# scan.net
KiCad netlist of a schematic drawn in EAGLE
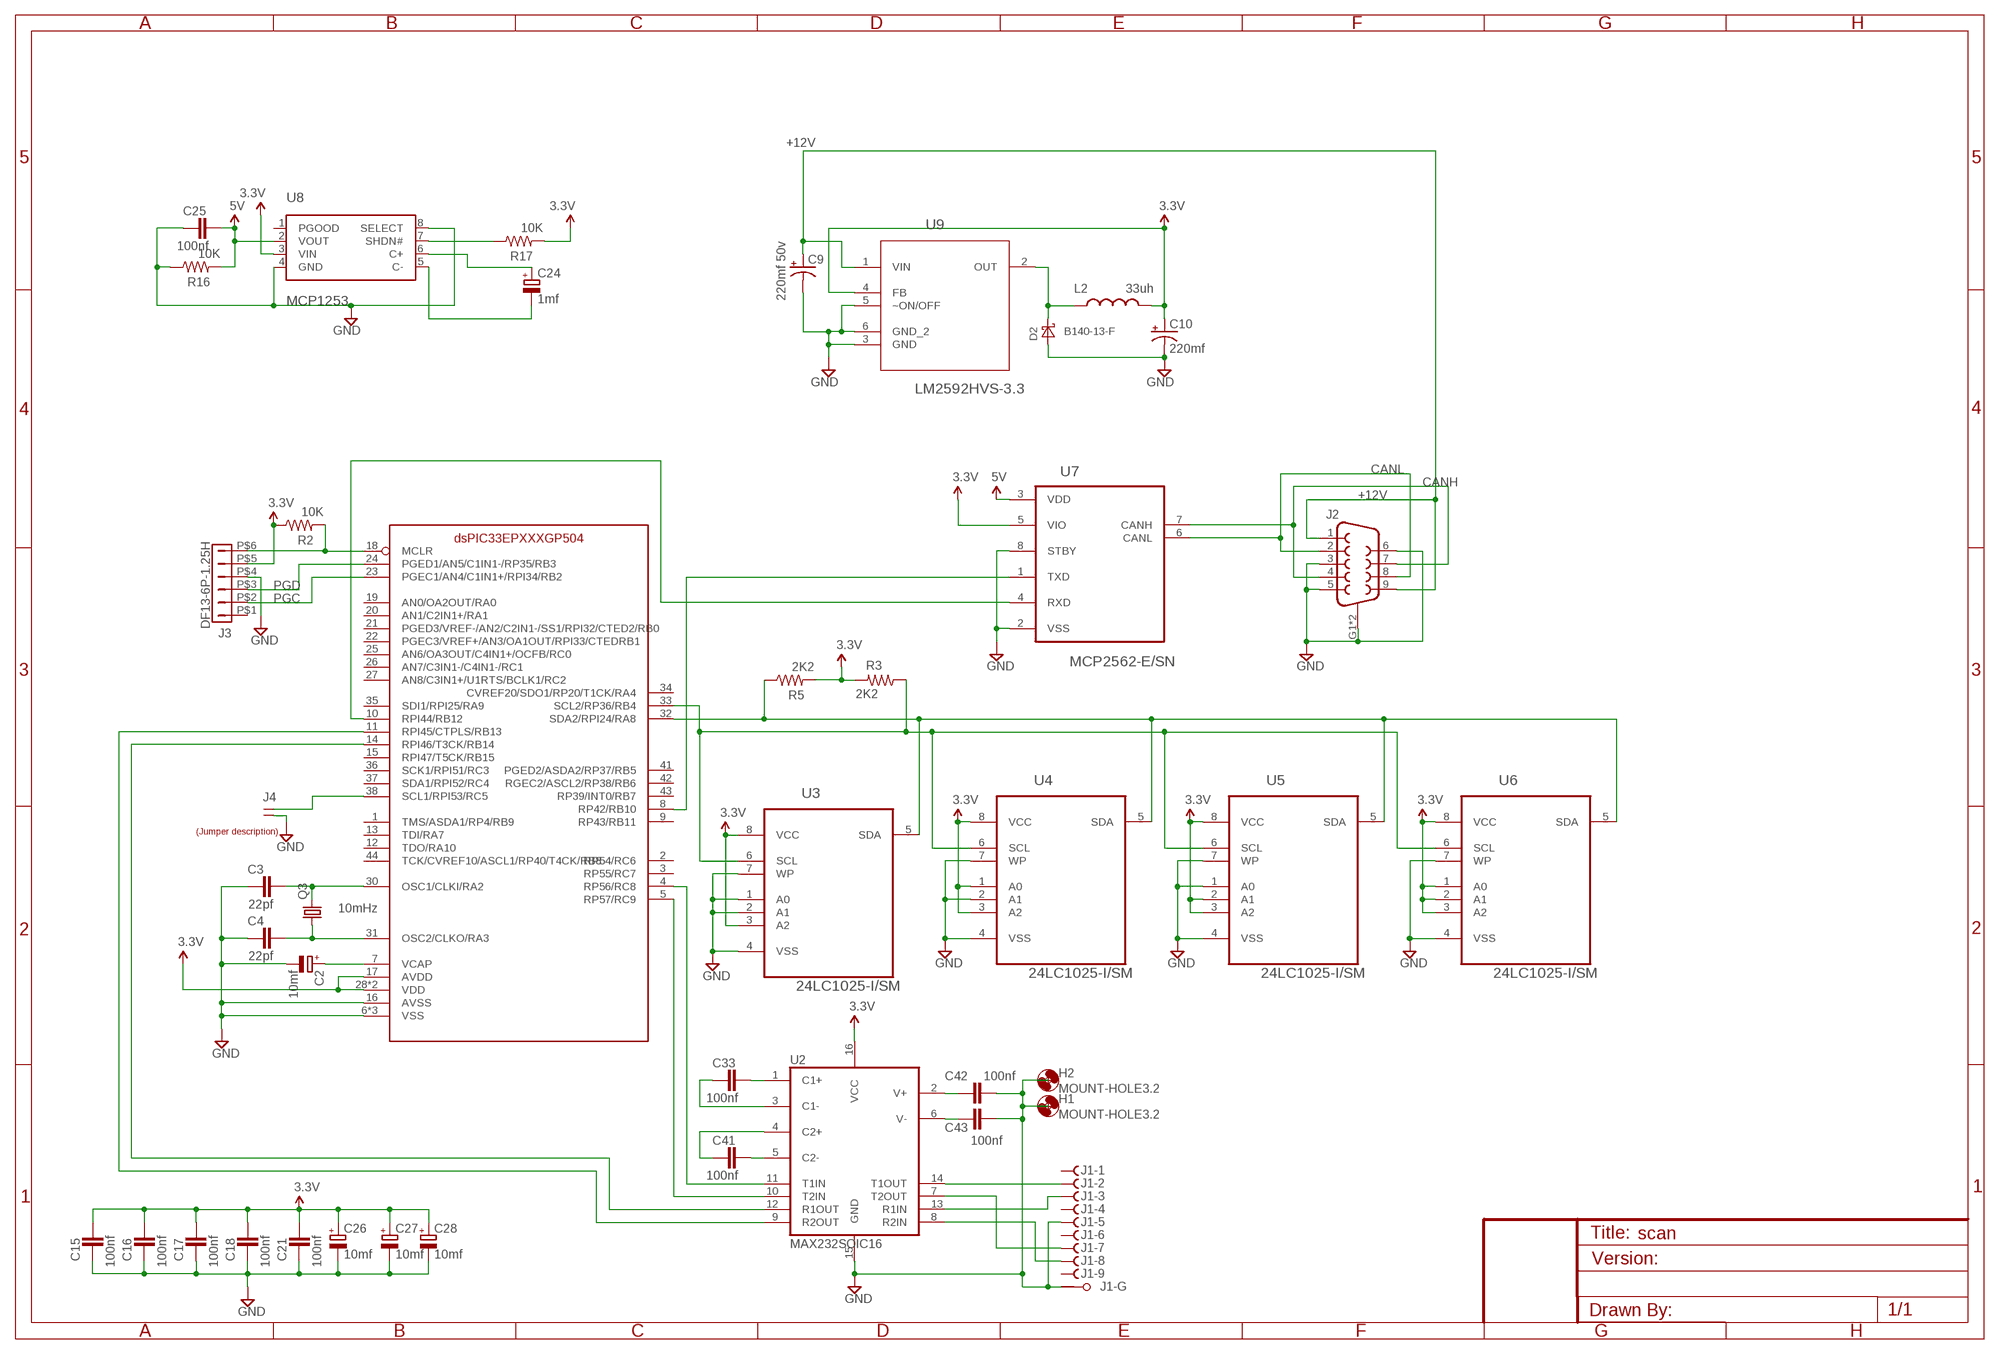
[diagram p0: schematic, sheet 1]

(export (version "E")
  (design (tool "Eeschema 10.0.6"))
  (components
    (comp (ref "C2")
      (value "10mf")
      (footprint "eagle-import:SMC_A")
      (fields (field (name "PARTNO") "T491A106K004AT"))
      (libsource (lib "eagle-import") (part "CAPACITOR_POL-SMC_A"))
    )
    (comp (ref "C3")
      (value "22pf")
      (footprint "eagle-import:C805")
      (fields (field (name "PARTNO") "C0805C220J5GACTU"))
      (libsource (lib "eagle-import") (part "CAPACITOR_NPOL-0805"))
    )
    (comp (ref "C4")
      (value "22pf")
      (footprint "eagle-import:C805")
      (fields (field (name "PARTNO") "C0805C220J5GACTU"))
      (libsource (lib "eagle-import") (part "CAPACITOR_NPOL-0805"))
    )
    (comp (ref "C9")
      (value "220mf 50v")
      (footprint "eagle-import:EIA7343")
      (fields (field (name "PARTNO") "T545X227M016ATE035"))
      (libsource (lib "eagle-import") (part "CAP_POL7343"))
    )
    (comp (ref "C10")
      (value "220mf")
      (footprint "eagle-import:EIA7343")
      (fields (field (name "PARTNO") "T545X227M016ATE035"))
      (libsource (lib "eagle-import") (part "CAP_POL7343"))
    )
    (comp (ref "C15")
      (value "100nf")
      (footprint "eagle-import:C805")
      (fields (field (name "PARTNO") "CL21F104ZBCNNNC"))
      (libsource (lib "eagle-import") (part "CAPACITOR_NPOL-0805"))
    )
    (comp (ref "C16")
      (value "100nf")
      (footprint "eagle-import:C805")
      (fields (field (name "PARTNO") "CL21F104ZBCNNNC"))
      (libsource (lib "eagle-import") (part "CAPACITOR_NPOL-0805"))
    )
    (comp (ref "C17")
      (value "100nf")
      (footprint "eagle-import:C805")
      (fields (field (name "PARTNO") "CL21F104ZBCNNNC"))
      (libsource (lib "eagle-import") (part "CAPACITOR_NPOL-0805"))
    )
    (comp (ref "C18")
      (value "100nf")
      (footprint "eagle-import:C805")
      (fields (field (name "PARTNO") "CL21F104ZBCNNNC"))
      (libsource (lib "eagle-import") (part "CAPACITOR_NPOL-0805"))
    )
    (comp (ref "C21")
      (value "100nf")
      (footprint "eagle-import:C805")
      (fields (field (name "PARTNO") "CL21F104ZBCNNNC"))
      (libsource (lib "eagle-import") (part "CAPACITOR_NPOL-0805"))
    )
    (comp (ref "C24")
      (value "1mf")
      (footprint "eagle-import:SMC_A")
      (fields (field (name "PARTNO") "F931C105MAA"))
      (libsource (lib "eagle-import") (part "CAPACITOR_POL-SMC_A"))
    )
    (comp (ref "C25")
      (value "100nf")
      (footprint "eagle-import:C805")
      (fields (field (name "PARTNO") "CL21F104ZBCNNNC"))
      (libsource (lib "eagle-import") (part "CAPACITOR_NPOL-0805"))
    )
    (comp (ref "C26")
      (value "10mf")
      (footprint "eagle-import:SMC_A")
      (fields (field (name "PARTNO") "T491A106K004AT"))
      (libsource (lib "eagle-import") (part "CAPACITOR_POL-SMC_A"))
    )
    (comp (ref "C27")
      (value "10mf")
      (footprint "eagle-import:SMC_A")
      (fields (field (name "PARTNO") "T491A106K004AT"))
      (libsource (lib "eagle-import") (part "CAPACITOR_POL-SMC_A"))
    )
    (comp (ref "C28")
      (value "10mf")
      (footprint "eagle-import:SMC_A")
      (fields (field (name "PARTNO") "T491A106K004AT"))
      (libsource (lib "eagle-import") (part "CAPACITOR_POL-SMC_A"))
    )
    (comp (ref "C33")
      (value "100nf")
      (footprint "eagle-import:C805")
      (fields (field (name "PARTNO") "CL21F104ZBCNNNC"))
      (libsource (lib "eagle-import") (part "CAPACITOR_NPOL-0805"))
    )
    (comp (ref "C41")
      (value "100nf")
      (footprint "eagle-import:C805")
      (fields (field (name "PARTNO") "CL21F104ZBCNNNC"))
      (libsource (lib "eagle-import") (part "CAPACITOR_NPOL-0805"))
    )
    (comp (ref "C42")
      (value "100nf")
      (footprint "eagle-import:C805")
      (fields (field (name "PARTNO") "CL21F104ZBCNNNC"))
      (libsource (lib "eagle-import") (part "CAPACITOR_NPOL-0805"))
    )
    (comp (ref "C43")
      (value "100nf")
      (footprint "eagle-import:C805")
      (fields (field (name "PARTNO") "CL21F104ZBCNNNC"))
      (libsource (lib "eagle-import") (part "CAPACITOR_NPOL-0805"))
    )
    (comp (ref "D2")
      (value "B140-13-F")
      (footprint "eagle-import:SMA")
      (libsource (lib "eagle-import") (part "DIODE-SCHOTTKY-SMA"))
    )
    (comp (ref "H1")
      (value "MOUNT-HOLE3.2")
      (footprint "eagle-import:3,2")
      (libsource (lib "eagle-import") (part "MOUNT-HOLE3.2"))
    )
    (comp (ref "H2")
      (value "MOUNT-HOLE3.2")
      (footprint "eagle-import:3,2")
      (libsource (lib "eagle-import") (part "MOUNT-HOLE3.2"))
    )
    (comp (ref "J1")
      (value "F09VPS")
      (footprint "eagle-import:F09VP")
      (fields (field (name "PARTNO") "3-1634222-2"))
      (libsource (lib "eagle-import") (part "F09VPS"))
    )
    (comp (ref "J2")
      (value "DB9FEMALE")
      (footprint "eagle-import:DB9")
      (fields (field (name "PARTNO") "1734354-2"))
      (libsource (lib "eagle-import") (part "DB9FEMALE"))
    )
    (comp (ref "J3")
      (value "DF13-6P-1.25H")
      (footprint "eagle-import:DF13A-6P-1.25H")
      (fields (field (name "PARTNO") "DF13A-6P-1.25H(20)"))
      (libsource (lib "eagle-import") (part "DF13-6P-1.25H"))
    )
    (comp (ref "J4")
      (value "JUMPER-1X2")
      (footprint "eagle-import:JUMPER-1X2")
      (fields (field (name "PARTNO") "M20-9770246"))
      (libsource (lib "eagle-import") (part "JUMPER-1X2"))
    )
    (comp (ref "L2")
      (value "33uh")
      (footprint "eagle-import:1812")
      (fields (field (name "PARTNO") "LQH43MN330K03L"))
      (libsource (lib "eagle-import") (part "INDUCTOR"))
    )
    (comp (ref "Q3")
      (value "10mHz")
      (footprint "eagle-import:HC49_S")
      (fields (field (name "PARTNO") "ATS100B-E"))
      (libsource (lib "eagle-import") (part "CRYSTALHC49S"))
    )
    (comp (ref "R2")
      (value "10K")
      (footprint "eagle-import:0603-RES")
      (fields (field (name "PARTNO") "RC0603FR-0710KL"))
      (libsource (lib "eagle-import") (part "RESISTOR0603-RES"))
    )
    (comp (ref "R3")
      (value "2K2")
      (footprint "eagle-import:0603-RES")
      (fields (field (name "PARTNO") "RC0603FR-072K2L"))
      (libsource (lib "eagle-import") (part "RESISTOR0603-RES"))
    )
    (comp (ref "R5")
      (value "2K2")
      (footprint "eagle-import:0603-RES")
      (fields (field (name "PARTNO") "RC0603FR-072K2L"))
      (libsource (lib "eagle-import") (part "RESISTOR0603-RES"))
    )
    (comp (ref "R16")
      (value "10K")
      (footprint "eagle-import:0603-RES")
      (fields (field (name "PARTNO") "RC0603FR-0710KL"))
      (libsource (lib "eagle-import") (part "RESISTOR0603-RES"))
    )
    (comp (ref "R17")
      (value "10K")
      (footprint "eagle-import:0603-RES")
      (fields (field (name "PARTNO") "RC0603FR-0710KL"))
      (libsource (lib "eagle-import") (part "RESISTOR0603-RES"))
    )
    (comp (ref "U$1")
      (value "LABEL_JUMPER_1X2")
      (footprint "eagle-import:JUMP2_DESC")
      (fields (field (name "OFF") "Normal") (field (name "ON") "Reset"))
      (libsource (lib "eagle-import") (part "LABEL_JUMPER_1X2"))
    )
    (comp (ref "U1")
      (value "DSPIC33EPXXXGP504")
      (footprint "eagle-import:TQFP44")
      (fields (field (name "PARTNO") "DSPIC33EP512GP504-I/PT"))
      (libsource (lib "eagle-import") (part "DSPIC33EPXXXGP504"))
    )
    (comp (ref "U2")
      (value "MAX232SOIC16")
      (footprint "eagle-import:SO016")
      (fields (field (name "PARTNO") "MAX3232ECDR"))
      (libsource (lib "eagle-import") (part "MAX232SOIC16"))
    )
    (comp (ref "U3")
      (value "24LC1025-I/SM")
      (footprint "eagle-import:SOIC8-N_MC")
      (fields (field (name "PARTNO") "24LC1025T-I/SN"))
      (libsource (lib "eagle-import") (part "24LC1025-I/SM"))
    )
    (comp (ref "U4")
      (value "24LC1025-I/SM")
      (footprint "eagle-import:SOIC8-N_MC")
      (fields (field (name "PARTNO") "24LC1025T-I/SN"))
      (libsource (lib "eagle-import") (part "24LC1025-I/SM"))
    )
    (comp (ref "U5")
      (value "24LC1025-I/SM")
      (footprint "eagle-import:SOIC8-N_MC")
      (fields (field (name "PARTNO") "24LC1025T-I/SN"))
      (libsource (lib "eagle-import") (part "24LC1025-I/SM"))
    )
    (comp (ref "U6")
      (value "24LC1025-I/SM")
      (footprint "eagle-import:SOIC8-N_MC")
      (fields (field (name "PARTNO") "24LC1025T-I/SN"))
      (libsource (lib "eagle-import") (part "24LC1025-I/SM"))
    )
    (comp (ref "U7")
      (value "MCP2562-E/SN")
      (footprint "eagle-import:SOIC-8N")
      (libsource (lib "eagle-import") (part "MCP2562-E/SN"))
    )
    (comp (ref "U8")
      (value "MCP1253")
      (footprint "eagle-import:MSOP8")
      (fields (field (name "PARTNO") "MCP1253-33X50I/MS"))
      (libsource (lib "eagle-import") (part "MCP1253"))
    )
    (comp (ref "U9")
      (value "LM2592HVS-3.3")
      (footprint "eagle-import:TO170P1435X457-5N")
      (fields (field (name "MPN") "LM2592HVS-5.0") (field (name "PARTNO") "LM2592HVSX-3.3/NOPB"))
      (libsource (lib "eagle-import") (part "LM2592HVS-5.0"))
    )
  )
  (nets
    (net (code "1") (name "/+12V") (class "Default")
      (node (ref "C9") (pin "A") (pinfunction "+_A") (pintype "passive"))
      (node (ref "J2") (pin "1") (pinfunction "1_1") (pintype "passive"))
      (node (ref "J2") (pin "9") (pinfunction "9_9") (pintype "passive"))
      (node (ref "U9") (pin "1") (pinfunction "VIN_1") (pintype "power_in"))
    )
    (net (code "2") (name "/CANH") (class "Default")
      (node (ref "J2") (pin "4") (pinfunction "4_4") (pintype "passive"))
      (node (ref "J2") (pin "7") (pinfunction "7_7") (pintype "passive"))
      (node (ref "U7") (pin "7") (pinfunction "CANH_7") (pintype "bidirectional"))
    )
    (net (code "3") (name "/CANL") (class "Default")
      (node (ref "J2") (pin "2") (pinfunction "2_2") (pintype "passive"))
      (node (ref "J2") (pin "8") (pinfunction "8_8") (pintype "passive"))
      (node (ref "U7") (pin "6") (pinfunction "CANL_6") (pintype "bidirectional"))
    )
    (net (code "4") (name "/PGC") (class "Default")
      (node (ref "J3") (pin "P$2") (pinfunction "2_P$2") (pintype "passive"))
      (node (ref "U1") (pin "23") (pinfunction "PGEC1/AN4/C1IN1+/RPI34/RB2_23") (pintype "bidirectional"))
    )
    (net (code "5") (name "/PGD") (class "Default")
      (node (ref "J3") (pin "P$3") (pinfunction "3_P$3") (pintype "passive"))
      (node (ref "U1") (pin "24") (pinfunction "PGED1/AN5/C1IN1-/RP35/RB3_24") (pintype "bidirectional"))
    )
    (net (code "6") (name "3.3V") (class "Default")
      (node (ref "C10") (pin "A") (pinfunction "+_A") (pintype "passive"))
      (node (ref "C15") (pin "1") (pinfunction "1_1") (pintype "passive"))
      (node (ref "C16") (pin "1") (pinfunction "1_1") (pintype "passive"))
      (node (ref "C17") (pin "1") (pinfunction "1_1") (pintype "passive"))
      (node (ref "C18") (pin "1") (pinfunction "1_1") (pintype "passive"))
      (node (ref "C21") (pin "1") (pinfunction "1_1") (pintype "passive"))
      (node (ref "C26") (pin "+") (pinfunction "+_+") (pintype "passive"))
      (node (ref "C27") (pin "+") (pinfunction "+_+") (pintype "passive"))
      (node (ref "C28") (pin "+") (pinfunction "+_+") (pintype "passive"))
      (node (ref "J3") (pin "P$5") (pinfunction "5_P$5") (pintype "passive"))
      (node (ref "L2") (pin "2") (pinfunction "2_2") (pintype "passive"))
      (node (ref "R17") (pin "2") (pinfunction "2_2") (pintype "passive"))
      (node (ref "R2") (pin "1") (pinfunction "1_1") (pintype "passive"))
      (node (ref "R3") (pin "2") (pinfunction "2_2") (pintype "passive"))
      (node (ref "R5") (pin "2") (pinfunction "2_2") (pintype "passive"))
      (node (ref "U1") (pin "17") (pinfunction "AVDD_17") (pintype "bidirectional"))
      (node (ref "U1") (pin "28") (pinfunction "VDD_28") (pintype "bidirectional"))
      (node (ref "U1") (pin "40") (pinfunction "VDD_40") (pintype "bidirectional"))
      (node (ref "U2") (pin "16") (pinfunction "VCC_16") (pintype "bidirectional"))
      (node (ref "U3") (pin "3") (pinfunction "A2_3") (pintype "input"))
      (node (ref "U3") (pin "8") (pinfunction "VCC_8") (pintype "power_in"))
      (node (ref "U4") (pin "1") (pinfunction "A0_1") (pintype "input"))
      (node (ref "U4") (pin "3") (pinfunction "A2_3") (pintype "input"))
      (node (ref "U4") (pin "8") (pinfunction "VCC_8") (pintype "power_in"))
      (node (ref "U5") (pin "2") (pinfunction "A1_2") (pintype "input"))
      (node (ref "U5") (pin "3") (pinfunction "A2_3") (pintype "input"))
      (node (ref "U5") (pin "8") (pinfunction "VCC_8") (pintype "power_in"))
      (node (ref "U6") (pin "1") (pinfunction "A0_1") (pintype "input"))
      (node (ref "U6") (pin "2") (pinfunction "A1_2") (pintype "input"))
      (node (ref "U6") (pin "3") (pinfunction "A2_3") (pintype "input"))
      (node (ref "U6") (pin "8") (pinfunction "VCC_8") (pintype "power_in"))
      (node (ref "U7") (pin "5") (pinfunction "VIO_5") (pintype "power_in"))
      (node (ref "U8") (pin "3") (pinfunction "VIN_3") (pintype "power_in"))
      (node (ref "U9") (pin "4") (pinfunction "FB_4") (pintype "input"))
    )
    (net (code "7") (name "5V") (class "Default")
      (node (ref "C25") (pin "1") (pinfunction "1_1") (pintype "passive"))
      (node (ref "R16") (pin "2") (pinfunction "2_2") (pintype "passive"))
      (node (ref "U7") (pin "3") (pinfunction "VDD_3") (pintype "power_in"))
      (node (ref "U8") (pin "2") (pinfunction "VOUT_2") (pintype "power_in"))
    )
    (net (code "8") (name "GND") (class "Default")
      (node (ref "C10") (pin "C") (pinfunction "-_C") (pintype "passive"))
      (node (ref "C15") (pin "2") (pinfunction "2_2") (pintype "passive"))
      (node (ref "C16") (pin "2") (pinfunction "2_2") (pintype "passive"))
      (node (ref "C17") (pin "2") (pinfunction "2_2") (pintype "passive"))
      (node (ref "C18") (pin "2") (pinfunction "2_2") (pintype "passive"))
      (node (ref "C2") (pin "-") (pinfunction "-_-") (pintype "passive"))
      (node (ref "C21") (pin "2") (pinfunction "2_2") (pintype "passive"))
      (node (ref "C25") (pin "2") (pinfunction "2_2") (pintype "passive"))
      (node (ref "C26") (pin "-") (pinfunction "-_-") (pintype "passive"))
      (node (ref "C27") (pin "-") (pinfunction "-_-") (pintype "passive"))
      (node (ref "C28") (pin "-") (pinfunction "-_-") (pintype "passive"))
      (node (ref "C3") (pin "2") (pinfunction "2_2") (pintype "passive"))
      (node (ref "C4") (pin "2") (pinfunction "2_2") (pintype "passive"))
      (node (ref "C42") (pin "1") (pinfunction "1_1") (pintype "passive"))
      (node (ref "C43") (pin "1") (pinfunction "1_1") (pintype "passive"))
      (node (ref "C9") (pin "C") (pinfunction "-_C") (pintype "passive"))
      (node (ref "D2") (pin "A") (pinfunction "A_A") (pintype "passive"))
      (node (ref "J1") (pin "5") (pinfunction "F_5") (pintype "passive"))
      (node (ref "J1") (pin "G1") (pinfunction "G1_G1") (pintype "passive"))
      (node (ref "J2") (pin "3") (pinfunction "3_3") (pintype "passive"))
      (node (ref "J2") (pin "5") (pinfunction "5_5") (pintype "passive"))
      (node (ref "J2") (pin "6") (pinfunction "6_6") (pintype "passive"))
      (node (ref "J2") (pin "G1") (pinfunction "SHIELD_G1") (pintype "power_in"))
      (node (ref "J2") (pin "G2") (pinfunction "SHIELD_G2") (pintype "power_in"))
      (node (ref "J3") (pin "P$4") (pinfunction "4_P$4") (pintype "passive"))
      (node (ref "J4") (pin "2") (pinfunction "2_2") (pintype "bidirectional"))
      (node (ref "R16") (pin "1") (pinfunction "1_1") (pintype "passive"))
      (node (ref "U1") (pin "16") (pinfunction "AVSS_16") (pintype "bidirectional"))
      (node (ref "U1") (pin "29") (pinfunction "VSS_29") (pintype "bidirectional"))
      (node (ref "U1") (pin "39") (pinfunction "VSS_39") (pintype "bidirectional"))
      (node (ref "U1") (pin "6") (pinfunction "VSS_6") (pintype "bidirectional"))
      (node (ref "U2") (pin "15") (pinfunction "GND_15") (pintype "bidirectional"))
      (node (ref "U3") (pin "1") (pinfunction "A0_1") (pintype "input"))
      (node (ref "U3") (pin "2") (pinfunction "A1_2") (pintype "input"))
      (node (ref "U3") (pin "4") (pinfunction "VSS_4") (pintype "passive"))
      (node (ref "U3") (pin "7") (pinfunction "WP_7") (pintype "input"))
      (node (ref "U4") (pin "2") (pinfunction "A1_2") (pintype "input"))
      (node (ref "U4") (pin "4") (pinfunction "VSS_4") (pintype "passive"))
      (node (ref "U4") (pin "7") (pinfunction "WP_7") (pintype "input"))
      (node (ref "U5") (pin "1") (pinfunction "A0_1") (pintype "input"))
      (node (ref "U5") (pin "4") (pinfunction "VSS_4") (pintype "passive"))
      (node (ref "U5") (pin "7") (pinfunction "WP_7") (pintype "input"))
      (node (ref "U6") (pin "4") (pinfunction "VSS_4") (pintype "passive"))
      (node (ref "U6") (pin "7") (pinfunction "WP_7") (pintype "input"))
      (node (ref "U7") (pin "2") (pinfunction "VSS_2") (pintype "power_in"))
      (node (ref "U7") (pin "8") (pinfunction "STBY_8") (pintype "input"))
      (node (ref "U8") (pin "4") (pinfunction "GND_4") (pintype "power_in"))
      (node (ref "U8") (pin "8") (pinfunction "SELECT_8") (pintype "input"))
      (node (ref "U9") (pin "3") (pinfunction "GND_3") (pintype "passive"))
      (node (ref "U9") (pin "5") (pinfunction "~{ON/OFF}_5") (pintype "input"))
      (node (ref "U9") (pin "6") (pinfunction "GND_2_6") (pintype "passive"))
    )
    (net (code "9") (name "Net-(J1B-F)") (class "Default")
      (node (ref "J1") (pin "2") (pinfunction "F_2") (pintype "passive"))
      (node (ref "U2") (pin "14") (pinfunction "T1OUT_14") (pintype "output"))
    )
    (net (code "10") (name "Net-(J1C-F)") (class "Default")
      (node (ref "J1") (pin "3") (pinfunction "F_3") (pintype "passive"))
      (node (ref "U2") (pin "13") (pinfunction "R1IN_13") (pintype "input"))
    )
    (net (code "11") (name "Net-(J1G-F)") (class "Default")
      (node (ref "J1") (pin "7") (pinfunction "F_7") (pintype "passive"))
      (node (ref "U2") (pin "7") (pinfunction "T2OUT_7") (pintype "output"))
    )
    (net (code "12") (name "Net-(J1H-F)") (class "Default")
      (node (ref "J1") (pin "8") (pinfunction "F_8") (pintype "passive"))
      (node (ref "U2") (pin "8") (pinfunction "R2IN_8") (pintype "input"))
    )
    (net (code "13") (name "Net-(J3-6)") (class "Default")
      (node (ref "J3") (pin "P$6") (pinfunction "6_P$6") (pintype "passive"))
      (node (ref "R2") (pin "2") (pinfunction "2_2") (pintype "passive"))
      (node (ref "U1") (pin "18") (pinfunction "MCLR_18") (pintype "input"))
    )
    (net (code "14") (name "Net-(U1-OSC1{slash}CLKI{slash}RA2)") (class "Default")
      (node (ref "C3") (pin "1") (pinfunction "1_1") (pintype "passive"))
      (node (ref "Q3") (pin "2") (pinfunction "2_2") (pintype "passive"))
      (node (ref "U1") (pin "30") (pinfunction "OSC1/CLKI/RA2_30") (pintype "bidirectional"))
    )
    (net (code "15") (name "Net-(U1-OSC2{slash}CLKO{slash}RA3)") (class "Default")
      (node (ref "C4") (pin "1") (pinfunction "1_1") (pintype "passive"))
      (node (ref "Q3") (pin "1") (pinfunction "1_1") (pintype "passive"))
      (node (ref "U1") (pin "31") (pinfunction "OSC2/CLKO/RA3_31") (pintype "bidirectional"))
    )
    (net (code "16") (name "Net-(U1-RP42{slash}RB10)") (class "Default")
      (node (ref "U1") (pin "8") (pinfunction "RP42/RB10_8") (pintype "bidirectional"))
      (node (ref "U7") (pin "1") (pinfunction "TXD_1") (pintype "input"))
    )
    (net (code "17") (name "Net-(U1-RP56{slash}RC8)") (class "Default")
      (node (ref "U1") (pin "4") (pinfunction "RP56/RC8_4") (pintype "bidirectional"))
      (node (ref "U2") (pin "11") (pinfunction "T1IN_11") (pintype "input"))
    )
    (net (code "18") (name "Net-(U1-RP57{slash}RC9)") (class "Default")
      (node (ref "U1") (pin "5") (pinfunction "RP57/RC9_5") (pintype "bidirectional"))
      (node (ref "U2") (pin "10") (pinfunction "T2IN_10") (pintype "input"))
    )
    (net (code "19") (name "Net-(U1-RPI44{slash}RB12)") (class "Default")
      (node (ref "U1") (pin "10") (pinfunction "RPI44/RB12_10") (pintype "bidirectional"))
      (node (ref "U7") (pin "4") (pinfunction "RXD_4") (pintype "output"))
    )
    (net (code "20") (name "Net-(U1-RPI45{slash}CTPLS{slash}RB13)") (class "Default")
      (node (ref "U1") (pin "11") (pinfunction "RPI45/CTPLS/RB13_11") (pintype "bidirectional"))
      (node (ref "U2") (pin "9") (pinfunction "R2OUT_9") (pintype "output"))
    )
    (net (code "21") (name "Net-(U1-RPI46{slash}T3CK{slash}RB14)") (class "Default")
      (node (ref "U1") (pin "14") (pinfunction "RPI46/T3CK/RB14_14") (pintype "bidirectional"))
      (node (ref "U2") (pin "12") (pinfunction "R1OUT_12") (pintype "output"))
    )
    (net (code "22") (name "Net-(U1-SCL1{slash}RPI53{slash}RC5)") (class "Default")
      (node (ref "J4") (pin "1") (pinfunction "1_1") (pintype "bidirectional"))
      (node (ref "U1") (pin "38") (pinfunction "SCL1/RPI53/RC5_38") (pintype "bidirectional"))
    )
    (net (code "23") (name "Net-(U1-SCL2{slash}RP36{slash}RB4)") (class "Default")
      (node (ref "R3") (pin "1") (pinfunction "1_1") (pintype "passive"))
      (node (ref "U1") (pin "33") (pinfunction "SCL2/RP36/RB4_33") (pintype "bidirectional"))
      (node (ref "U3") (pin "6") (pinfunction "SCL_6") (pintype "input"))
      (node (ref "U4") (pin "6") (pinfunction "SCL_6") (pintype "input"))
      (node (ref "U5") (pin "6") (pinfunction "SCL_6") (pintype "input"))
      (node (ref "U6") (pin "6") (pinfunction "SCL_6") (pintype "input"))
    )
    (net (code "24") (name "Net-(U1-SDA2{slash}RPI24{slash}RA8)") (class "Default")
      (node (ref "R5") (pin "1") (pinfunction "1_1") (pintype "passive"))
      (node (ref "U1") (pin "32") (pinfunction "SDA2/RPI24/RA8_32") (pintype "bidirectional"))
      (node (ref "U3") (pin "5") (pinfunction "SDA_5") (pintype "bidirectional"))
      (node (ref "U4") (pin "5") (pinfunction "SDA_5") (pintype "bidirectional"))
      (node (ref "U5") (pin "5") (pinfunction "SDA_5") (pintype "bidirectional"))
      (node (ref "U6") (pin "5") (pinfunction "SDA_5") (pintype "bidirectional"))
    )
    (net (code "25") (name "Net-(U1-VCAP)") (class "Default")
      (node (ref "C2") (pin "+") (pinfunction "+_+") (pintype "passive"))
      (node (ref "U1") (pin "7") (pinfunction "VCAP_7") (pintype "bidirectional"))
    )
    (net (code "26") (name "Net-(U2-C1+)") (class "Default")
      (node (ref "C33") (pin "1") (pinfunction "1_1") (pintype "passive"))
      (node (ref "U2") (pin "1") (pinfunction "C1+_1") (pintype "bidirectional"))
    )
    (net (code "27") (name "Net-(U2-C1-)") (class "Default")
      (node (ref "C33") (pin "2") (pinfunction "2_2") (pintype "passive"))
      (node (ref "U2") (pin "3") (pinfunction "C1-_3") (pintype "bidirectional"))
    )
    (net (code "28") (name "Net-(U2-C2+)") (class "Default")
      (node (ref "C41") (pin "2") (pinfunction "2_2") (pintype "passive"))
      (node (ref "U2") (pin "4") (pinfunction "C2+_4") (pintype "bidirectional"))
    )
    (net (code "29") (name "Net-(U2-C2-)") (class "Default")
      (node (ref "C41") (pin "1") (pinfunction "1_1") (pintype "passive"))
      (node (ref "U2") (pin "5") (pinfunction "C2-_5") (pintype "bidirectional"))
    )
    (net (code "30") (name "Net-(U2-V+)") (class "Default")
      (node (ref "C42") (pin "2") (pinfunction "2_2") (pintype "passive"))
      (node (ref "U2") (pin "2") (pinfunction "V+_2") (pintype "bidirectional"))
    )
    (net (code "31") (name "Net-(U2-V-)") (class "Default")
      (node (ref "C43") (pin "2") (pinfunction "2_2") (pintype "passive"))
      (node (ref "U2") (pin "6") (pinfunction "V-_6") (pintype "bidirectional"))
    )
    (net (code "32") (name "Net-(U8-C+)") (class "Default")
      (node (ref "C24") (pin "+") (pinfunction "+_+") (pintype "passive"))
      (node (ref "U8") (pin "6") (pinfunction "C+_6") (pintype "passive"))
    )
    (net (code "33") (name "Net-(U8-C-)") (class "Default")
      (node (ref "C24") (pin "-") (pinfunction "-_-") (pintype "passive"))
      (node (ref "U8") (pin "5") (pinfunction "C-_5") (pintype "passive"))
    )
    (net (code "34") (name "Net-(U8-SHDN#)") (class "Default")
      (node (ref "R17") (pin "1") (pinfunction "1_1") (pintype "passive"))
      (node (ref "U8") (pin "7") (pinfunction "SHDN#_7") (pintype "input"))
    )
    (net (code "35") (name "Net-(U9-OUT)") (class "Default")
      (node (ref "D2") (pin "C") (pinfunction "C_C") (pintype "passive"))
      (node (ref "L2") (pin "1") (pinfunction "1_1") (pintype "passive"))
      (node (ref "U9") (pin "2") (pinfunction "OUT_2") (pintype "output"))
    )
    (net (code "36") (name "unconnected-(J1-PadG2)") (class "Default")
      (node (ref "J1") (pin "G2") (pinfunction "G2_G2") (pintype "passive"))
    )
    (net (code "37") (name "unconnected-(J1A-F-Pad1)") (class "Default")
      (node (ref "J1") (pin "1") (pinfunction "F_1") (pintype "passive"))
    )
    (net (code "38") (name "unconnected-(J1D-F-Pad4)") (class "Default")
      (node (ref "J1") (pin "4") (pinfunction "F_4") (pintype "passive"))
    )
    (net (code "39") (name "unconnected-(J1F-F-Pad6)") (class "Default")
      (node (ref "J1") (pin "6") (pinfunction "F_6") (pintype "passive"))
    )
    (net (code "40") (name "unconnected-(J1I-F-Pad9)") (class "Default")
      (node (ref "J1") (pin "9") (pinfunction "F_9") (pintype "passive"))
    )
    (net (code "41") (name "unconnected-(J3-1-PadP$1)") (class "Default")
      (node (ref "J3") (pin "P$1") (pinfunction "1_P$1") (pintype "passive"))
    )
    (net (code "42") (name "unconnected-(U1-AN0{slash}OA2OUT{slash}RA0-Pad19)") (class "Default")
      (node (ref "U1") (pin "19") (pinfunction "AN0/OA2OUT/RA0_19") (pintype "bidirectional"))
    )
    (net (code "43") (name "unconnected-(U1-AN1{slash}C2IN1+{slash}RA1-Pad20)") (class "Default")
      (node (ref "U1") (pin "20") (pinfunction "AN1/C2IN1+/RA1_20") (pintype "bidirectional"))
    )
    (net (code "44") (name "unconnected-(U1-AN6{slash}OA3OUT{slash}C4IN1+{slash}OCFB{slash}RC0-Pad25)") (class "Default")
      (node (ref "U1") (pin "25") (pinfunction "AN6/OA3OUT/C4IN1+/OCFB/RC0_25") (pintype "bidirectional"))
    )
    (net (code "45") (name "unconnected-(U1-AN7{slash}C3IN1-{slash}C4IN1-{slash}RC1-Pad26)") (class "Default")
      (node (ref "U1") (pin "26") (pinfunction "AN7/C3IN1-/C4IN1-/RC1_26") (pintype "bidirectional"))
    )
    (net (code "46") (name "unconnected-(U1-AN8{slash}C3IN1+{slash}U1RTS{slash}BCLK1{slash}RC2-Pad27)") (class "Default")
      (node (ref "U1") (pin "27") (pinfunction "AN8/C3IN1+/U1RTS/BCLK1/RC2_27") (pintype "bidirectional"))
    )
    (net (code "47") (name "unconnected-(U1-CVREF20{slash}SDO1{slash}RP20{slash}T1CK{slash}RA4-Pad34)") (class "Default")
      (node (ref "U1") (pin "34") (pinfunction "CVREF20/SDO1/RP20/T1CK/RA4_34") (pintype "bidirectional"))
    )
    (net (code "48") (name "unconnected-(U1-PGEC3{slash}VREF+{slash}AN3{slash}OA1OUT{slash}RPI33{slash}CTEDRB1-Pad22)") (class "Default")
      (node (ref "U1") (pin "22") (pinfunction "PGEC3/VREF+/AN3/OA1OUT/RPI33/CTEDRB1_22") (pintype "bidirectional"))
    )
    (net (code "49") (name "unconnected-(U1-PGED2{slash}ASDA2{slash}RP37{slash}RB5-Pad41)") (class "Default")
      (node (ref "U1") (pin "41") (pinfunction "PGED2/ASDA2/RP37/RB5_41") (pintype "bidirectional"))
    )
    (net (code "50") (name "unconnected-(U1-PGED3{slash}VREF-{slash}AN2{slash}C2IN1-{slash}SS1{slash}RPI32{slash}CTED2{slash}RB0-Pad21)") (class "Default")
      (node (ref "U1") (pin "21") (pinfunction "PGED3/VREF-/AN2/C2IN1-/SS1/RPI32/CTED2/RB0_21") (pintype "bidirectional"))
    )
    (net (code "51") (name "unconnected-(U1-RGEC2{slash}ASCL2{slash}RP38{slash}RB6-Pad42)") (class "Default")
      (node (ref "U1") (pin "42") (pinfunction "RGEC2/ASCL2/RP38/RB6_42") (pintype "bidirectional"))
    )
    (net (code "52") (name "unconnected-(U1-RP39{slash}INT0{slash}RB7-Pad43)") (class "Default")
      (node (ref "U1") (pin "43") (pinfunction "RP39/INT0/RB7_43") (pintype "bidirectional"))
    )
    (net (code "53") (name "unconnected-(U1-RP43{slash}RB11-Pad9)") (class "Default")
      (node (ref "U1") (pin "9") (pinfunction "RP43/RB11_9") (pintype "bidirectional"))
    )
    (net (code "54") (name "unconnected-(U1-RP54{slash}RC6-Pad2)") (class "Default")
      (node (ref "U1") (pin "2") (pinfunction "RP54/RC6_2") (pintype "bidirectional"))
    )
    (net (code "55") (name "unconnected-(U1-RP55{slash}RC7-Pad3)") (class "Default")
      (node (ref "U1") (pin "3") (pinfunction "RP55/RC7_3") (pintype "bidirectional"))
    )
    (net (code "56") (name "unconnected-(U1-RPI47{slash}T5CK{slash}RB15-Pad15)") (class "Default")
      (node (ref "U1") (pin "15") (pinfunction "RPI47/T5CK/RB15_15") (pintype "bidirectional"))
    )
    (net (code "57") (name "unconnected-(U1-SCK1{slash}RPI51{slash}RC3-Pad36)") (class "Default")
      (node (ref "U1") (pin "36") (pinfunction "SCK1/RPI51/RC3_36") (pintype "bidirectional"))
    )
    (net (code "58") (name "unconnected-(U1-SDA1{slash}RPI52{slash}RC4-Pad37)") (class "Default")
      (node (ref "U1") (pin "37") (pinfunction "SDA1/RPI52/RC4_37") (pintype "bidirectional"))
    )
    (net (code "59") (name "unconnected-(U1-SDI1{slash}RPI25{slash}RA9-Pad35)") (class "Default")
      (node (ref "U1") (pin "35") (pinfunction "SDI1/RPI25/RA9_35") (pintype "bidirectional"))
    )
    (net (code "60") (name "unconnected-(U1-TCK{slash}CVREF10{slash}ASCL1{slash}RP40{slash}T4CK{slash}RB8-Pad44)") (class "Default")
      (node (ref "U1") (pin "44") (pinfunction "TCK/CVREF10/ASCL1/RP40/T4CK/RB8_44") (pintype "bidirectional"))
    )
    (net (code "61") (name "unconnected-(U1-TDI{slash}RA7-Pad13)") (class "Default")
      (node (ref "U1") (pin "13") (pinfunction "TDI/RA7_13") (pintype "bidirectional"))
    )
    (net (code "62") (name "unconnected-(U1-TDO{slash}RA10-Pad12)") (class "Default")
      (node (ref "U1") (pin "12") (pinfunction "TDO/RA10_12") (pintype "bidirectional"))
    )
    (net (code "63") (name "unconnected-(U1-TMS{slash}ASDA1{slash}RP4{slash}RB9-Pad1)") (class "Default")
      (node (ref "U1") (pin "1") (pinfunction "TMS/ASDA1/RP4/RB9_1") (pintype "bidirectional"))
    )
    (net (code "64") (name "unconnected-(U8-PGOOD-Pad1)") (class "Default")
      (node (ref "U8") (pin "1") (pinfunction "PGOOD_1") (pintype "open_collector"))
    )
  )
)
